# Interrupter.net
KiCad netlist of a schematic drawn in EAGLE
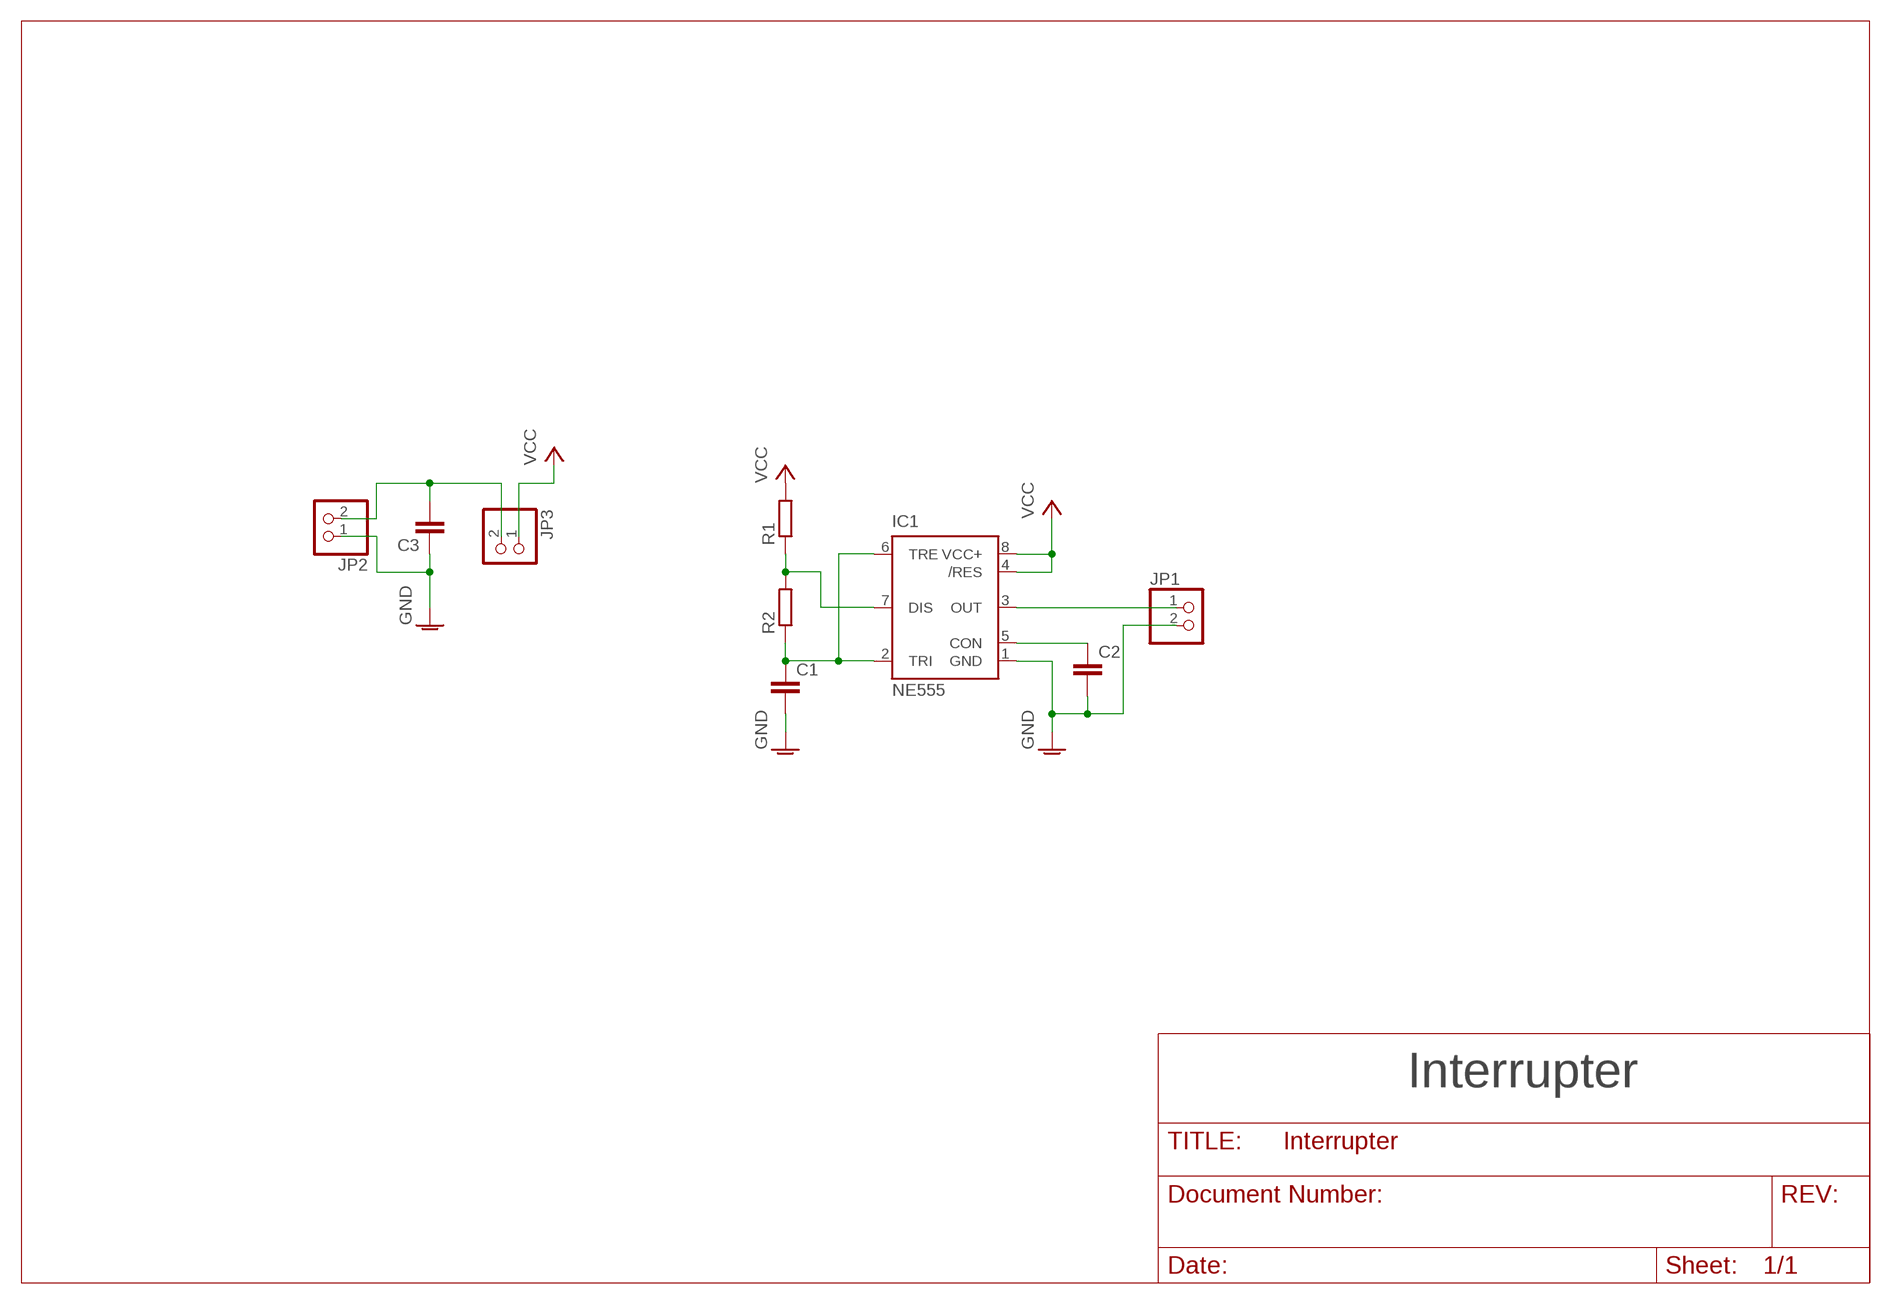
[diagram p0: schematic, sheet 1]

(export (version "E")
  (design (tool "Eeschema 10.0.6"))
  (components
    (comp (ref "C1")
      (value "C-EUC0603")
      (footprint "eagle-import:C0603")
      (libsource (lib "eagle-import") (part "C-EUC0603"))
    )
    (comp (ref "C2")
      (value "C-EUC0603")
      (footprint "eagle-import:C0603")
      (libsource (lib "eagle-import") (part "C-EUC0603"))
    )
    (comp (ref "C3")
      (value "C-EUC0603")
      (footprint "eagle-import:C0603")
      (libsource (lib "eagle-import") (part "C-EUC0603"))
    )
    (comp (ref "IC1")
      (value "NE555")
      (footprint "eagle-import:DIL-08")
      (fields (field (name "MF") "Arrow Electronics") (field (name "MPN") "NE555N"))
      (libsource (lib "eagle-import") (part "NE555"))
    )
    (comp (ref "JP1")
      (value "PINHD-1X2")
      (footprint "eagle-import:1X02")
      (libsource (lib "eagle-import") (part "PINHD-1X2"))
    )
    (comp (ref "JP2")
      (value "PINHD-1X2")
      (footprint "eagle-import:1X02")
      (libsource (lib "eagle-import") (part "PINHD-1X2"))
    )
    (comp (ref "JP3")
      (value "PINHD-1X2")
      (footprint "eagle-import:1X02")
      (libsource (lib "eagle-import") (part "PINHD-1X2"))
    )
    (comp (ref "R1")
      (value "R-EU_R0603")
      (footprint "eagle-import:R0603")
      (libsource (lib "eagle-import") (part "R-EU_R0603"))
    )
    (comp (ref "R2")
      (value "R-EU_R0603")
      (footprint "eagle-import:R0603")
      (libsource (lib "eagle-import") (part "R-EU_R0603"))
    )
  )
  (nets
    (net (code "1") (name "GND") (class "Default")
      (node (ref "C1") (pin "2") (pinfunction "2_2") (pintype "passive"))
      (node (ref "C2") (pin "2") (pinfunction "2_2") (pintype "passive"))
      (node (ref "C3") (pin "1") (pinfunction "1_1") (pintype "passive"))
      (node (ref "IC1") (pin "1") (pinfunction "GND_1") (pintype "power_in"))
      (node (ref "JP1") (pin "2") (pinfunction "2_2") (pintype "passive"))
      (node (ref "JP2") (pin "1") (pinfunction "1_1") (pintype "passive"))
    )
    (net (code "2") (name "Net-(C3-Pad2)") (class "Default")
      (node (ref "C3") (pin "2") (pinfunction "2_2") (pintype "passive"))
      (node (ref "JP2") (pin "2") (pinfunction "2_2") (pintype "passive"))
      (node (ref "JP3") (pin "2") (pinfunction "2_2") (pintype "passive"))
    )
    (net (code "3") (name "Net-(IC1-CON)") (class "Default")
      (node (ref "C2") (pin "1") (pinfunction "1_1") (pintype "passive"))
      (node (ref "IC1") (pin "5") (pinfunction "CON_5") (pintype "input"))
    )
    (net (code "4") (name "Net-(IC1-DIS)") (class "Default")
      (node (ref "IC1") (pin "7") (pinfunction "DIS_7") (pintype "input"))
      (node (ref "R1") (pin "1") (pinfunction "1_1") (pintype "passive"))
      (node (ref "R2") (pin "2") (pinfunction "2_2") (pintype "passive"))
    )
    (net (code "5") (name "Net-(IC1-OUT)") (class "Default")
      (node (ref "IC1") (pin "3") (pinfunction "OUT_3") (pintype "output"))
      (node (ref "JP1") (pin "1") (pinfunction "1_1") (pintype "passive"))
    )
    (net (code "6") (name "Net-(IC1-TRE)") (class "Default")
      (node (ref "C1") (pin "1") (pinfunction "1_1") (pintype "passive"))
      (node (ref "IC1") (pin "2") (pinfunction "TRI_2") (pintype "input"))
      (node (ref "IC1") (pin "6") (pinfunction "TRE_6") (pintype "input"))
      (node (ref "R2") (pin "1") (pinfunction "1_1") (pintype "passive"))
    )
    (net (code "7") (name "VCC") (class "Default")
      (node (ref "IC1") (pin "4") (pinfunction "/RES_4") (pintype "input"))
      (node (ref "IC1") (pin "8") (pinfunction "VCC+_8") (pintype "power_in"))
      (node (ref "JP3") (pin "1") (pinfunction "1_1") (pintype "passive"))
      (node (ref "R1") (pin "2") (pinfunction "2_2") (pintype "passive"))
    )
  )
)
